# central__board.net
KiCad netlist of a schematic drawn in EAGLE
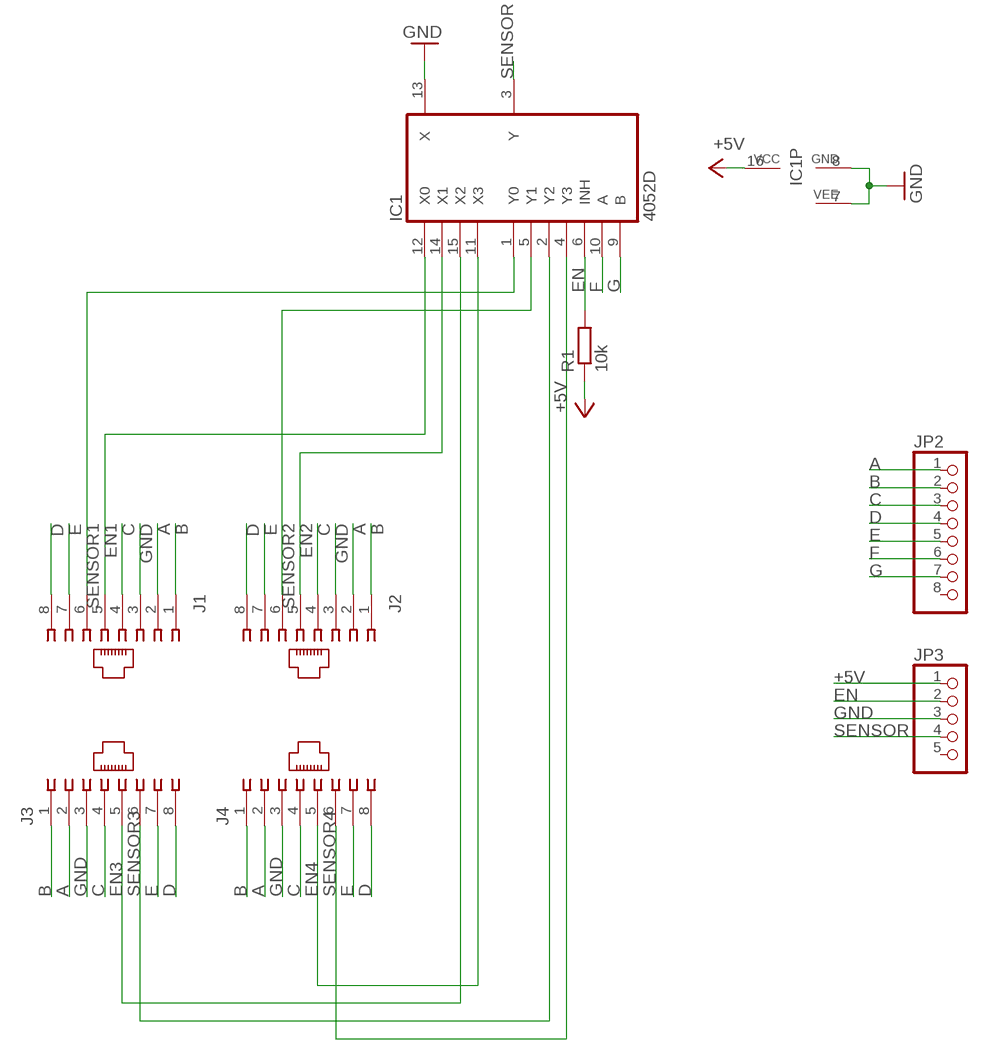
[diagram p0: schematic, sheet 1]

(export (version "E")
  (design (tool "Eeschema 10.0.6"))
  (components
    (comp (ref "IC1")
      (value "4052D")
      (footprint "eagle-import:SO16")
      (libsource (lib "eagle-import") (part "4052D"))
    )
    (comp (ref "J1")
      (value "556416-1")
      (footprint "eagle-import:556416-1")
      (libsource (lib "eagle-import") (part "556416-1"))
    )
    (comp (ref "J2")
      (value "556416-1")
      (footprint "eagle-import:556416-1")
      (libsource (lib "eagle-import") (part "556416-1"))
    )
    (comp (ref "J3")
      (value "556416-1")
      (footprint "eagle-import:556416-1")
      (libsource (lib "eagle-import") (part "556416-1"))
    )
    (comp (ref "J4")
      (value "556416-1")
      (footprint "eagle-import:556416-1")
      (libsource (lib "eagle-import") (part "556416-1"))
    )
    (comp (ref "JP2")
      (value "PINHD-1X8")
      (footprint "eagle-import:1X08")
      (libsource (lib "eagle-import") (part "PINHD-1X8"))
    )
    (comp (ref "JP3")
      (value "PINHD-1X5")
      (footprint "eagle-import:1X05")
      (libsource (lib "eagle-import") (part "PINHD-1X5"))
    )
    (comp (ref "R1")
      (value "10k")
      (footprint "eagle-import:M1206")
      (libsource (lib "eagle-import") (part "R-EU_M1206"))
    )
  )
  (nets
    (net (code "1") (name "+5V") (class "Default")
      (node (ref "IC1") (pin "16") (pinfunction "VCC_16") (pintype "power_in"))
      (node (ref "JP3") (pin "1") (pinfunction "1_1") (pintype "passive"))
      (node (ref "R1") (pin "1") (pinfunction "1_1") (pintype "passive"))
    )
    (net (code "2") (name "/A") (class "Default")
      (node (ref "J1") (pin "2") (pinfunction "2_2") (pintype "passive"))
      (node (ref "J2") (pin "2") (pinfunction "2_2") (pintype "passive"))
      (node (ref "J3") (pin "2") (pinfunction "2_2") (pintype "passive"))
      (node (ref "J4") (pin "2") (pinfunction "2_2") (pintype "passive"))
      (node (ref "JP2") (pin "1") (pinfunction "1_1") (pintype "passive"))
    )
    (net (code "3") (name "/B") (class "Default")
      (node (ref "J1") (pin "1") (pinfunction "1_1") (pintype "passive"))
      (node (ref "J2") (pin "1") (pinfunction "1_1") (pintype "passive"))
      (node (ref "J3") (pin "1") (pinfunction "1_1") (pintype "passive"))
      (node (ref "J4") (pin "1") (pinfunction "1_1") (pintype "passive"))
      (node (ref "JP2") (pin "2") (pinfunction "2_2") (pintype "passive"))
    )
    (net (code "4") (name "/C") (class "Default")
      (node (ref "J1") (pin "4") (pinfunction "4_4") (pintype "passive"))
      (node (ref "J2") (pin "4") (pinfunction "4_4") (pintype "passive"))
      (node (ref "J3") (pin "4") (pinfunction "4_4") (pintype "passive"))
      (node (ref "J4") (pin "4") (pinfunction "4_4") (pintype "passive"))
      (node (ref "JP2") (pin "3") (pinfunction "3_3") (pintype "passive"))
    )
    (net (code "5") (name "/D") (class "Default")
      (node (ref "J1") (pin "8") (pinfunction "8_8") (pintype "passive"))
      (node (ref "J2") (pin "8") (pinfunction "8_8") (pintype "passive"))
      (node (ref "J3") (pin "8") (pinfunction "8_8") (pintype "passive"))
      (node (ref "J4") (pin "8") (pinfunction "8_8") (pintype "passive"))
      (node (ref "JP2") (pin "4") (pinfunction "4_4") (pintype "passive"))
    )
    (net (code "6") (name "/E") (class "Default")
      (node (ref "J1") (pin "7") (pinfunction "7_7") (pintype "passive"))
      (node (ref "J2") (pin "7") (pinfunction "7_7") (pintype "passive"))
      (node (ref "J3") (pin "7") (pinfunction "7_7") (pintype "passive"))
      (node (ref "J4") (pin "7") (pinfunction "7_7") (pintype "passive"))
      (node (ref "JP2") (pin "5") (pinfunction "5_5") (pintype "passive"))
    )
    (net (code "7") (name "/EN") (class "Default")
      (node (ref "IC1") (pin "6") (pinfunction "INH_6") (pintype "input"))
      (node (ref "JP3") (pin "2") (pinfunction "2_2") (pintype "passive"))
      (node (ref "R1") (pin "2") (pinfunction "2_2") (pintype "passive"))
    )
    (net (code "8") (name "/EN1") (class "Default")
      (node (ref "IC1") (pin "12") (pinfunction "X0_12") (pintype "bidirectional"))
      (node (ref "J1") (pin "5") (pinfunction "5_5") (pintype "passive"))
    )
    (net (code "9") (name "/EN2") (class "Default")
      (node (ref "IC1") (pin "14") (pinfunction "X1_14") (pintype "bidirectional"))
      (node (ref "J2") (pin "5") (pinfunction "5_5") (pintype "passive"))
    )
    (net (code "10") (name "/EN3") (class "Default")
      (node (ref "IC1") (pin "15") (pinfunction "X2_15") (pintype "bidirectional"))
      (node (ref "J3") (pin "5") (pinfunction "5_5") (pintype "passive"))
    )
    (net (code "11") (name "/EN4") (class "Default")
      (node (ref "IC1") (pin "11") (pinfunction "X3_11") (pintype "bidirectional"))
      (node (ref "J4") (pin "5") (pinfunction "5_5") (pintype "passive"))
    )
    (net (code "12") (name "/F") (class "Default")
      (node (ref "IC1") (pin "10") (pinfunction "A_10") (pintype "input"))
      (node (ref "JP2") (pin "6") (pinfunction "6_6") (pintype "passive"))
    )
    (net (code "13") (name "/G") (class "Default")
      (node (ref "IC1") (pin "9") (pinfunction "B_9") (pintype "input"))
      (node (ref "JP2") (pin "7") (pinfunction "7_7") (pintype "passive"))
    )
    (net (code "14") (name "/SENSOR") (class "Default")
      (node (ref "IC1") (pin "3") (pinfunction "Y_3") (pintype "bidirectional"))
      (node (ref "JP3") (pin "4") (pinfunction "4_4") (pintype "passive"))
    )
    (net (code "15") (name "/SENSOR1") (class "Default")
      (node (ref "IC1") (pin "1") (pinfunction "Y0_1") (pintype "bidirectional"))
      (node (ref "J1") (pin "6") (pinfunction "6_6") (pintype "passive"))
    )
    (net (code "16") (name "/SENSOR2") (class "Default")
      (node (ref "IC1") (pin "5") (pinfunction "Y1_5") (pintype "bidirectional"))
      (node (ref "J2") (pin "6") (pinfunction "6_6") (pintype "passive"))
    )
    (net (code "17") (name "/SENSOR3") (class "Default")
      (node (ref "IC1") (pin "2") (pinfunction "Y2_2") (pintype "bidirectional"))
      (node (ref "J3") (pin "6") (pinfunction "6_6") (pintype "passive"))
    )
    (net (code "18") (name "/SENSOR4") (class "Default")
      (node (ref "IC1") (pin "4") (pinfunction "Y3_4") (pintype "bidirectional"))
      (node (ref "J4") (pin "6") (pinfunction "6_6") (pintype "passive"))
    )
    (net (code "19") (name "GND") (class "Default")
      (node (ref "IC1") (pin "13") (pinfunction "X_13") (pintype "bidirectional"))
      (node (ref "IC1") (pin "7") (pinfunction "VEE_7") (pintype "power_in"))
      (node (ref "IC1") (pin "8") (pinfunction "GND_8") (pintype "power_in"))
      (node (ref "J1") (pin "3") (pinfunction "3_3") (pintype "passive"))
      (node (ref "J2") (pin "3") (pinfunction "3_3") (pintype "passive"))
      (node (ref "J3") (pin "3") (pinfunction "3_3") (pintype "passive"))
      (node (ref "J4") (pin "3") (pinfunction "3_3") (pintype "passive"))
      (node (ref "JP3") (pin "3") (pinfunction "3_3") (pintype "passive"))
    )
    (net (code "20") (name "unconnected-(JP2-Pad8)") (class "Default")
      (node (ref "JP2") (pin "8") (pinfunction "8_8") (pintype "passive"))
    )
    (net (code "21") (name "unconnected-(JP3-Pad5)") (class "Default")
      (node (ref "JP3") (pin "5") (pinfunction "5_5") (pintype "passive"))
    )
  )
)
